# Master_sheet.net
KiCad netlist of a schematic drawn in Altium Designer
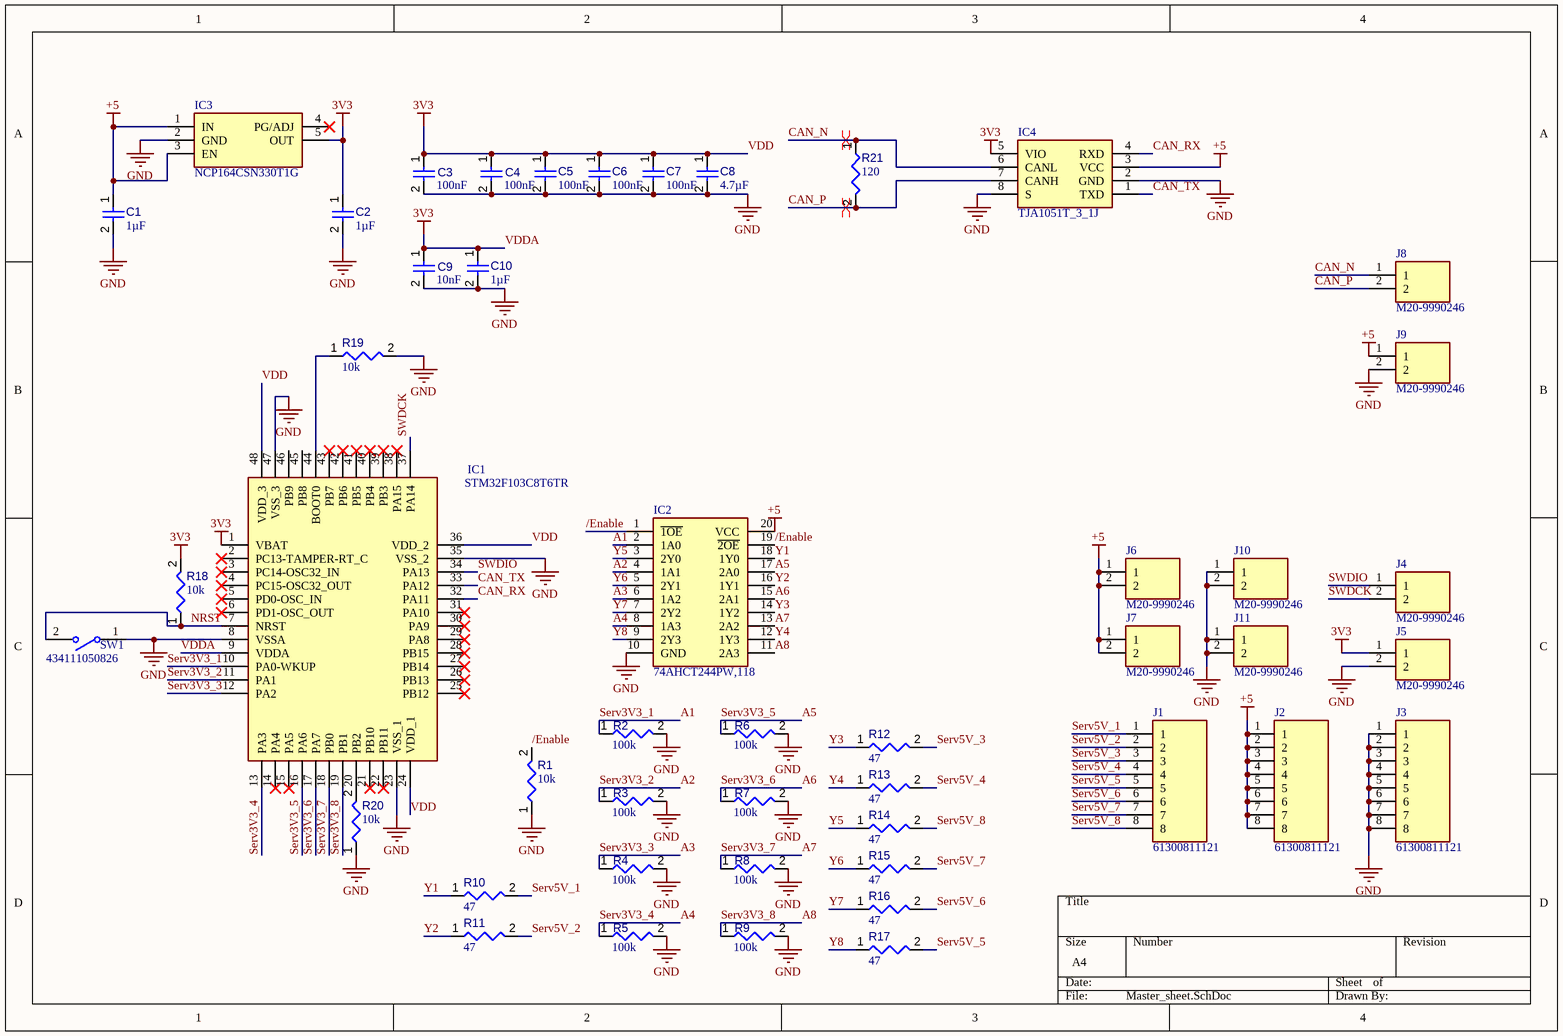
[diagram p0: Master_sheet.SchDoc]

(export (version "E")
  (design (tool "Eeschema 10.0.6"))
  (components
    (comp (ref "C1")
      (value "1µF")
      (footprint "CAPC1608X94X35NL15T15")
      (description "Chip Capacitor, 1 uF, +/- 10%, 16 V, 0603 (1608 Metric)")
      (fields (field (name "TOLERANCE") "10%") (field (name "Comment") "Capacitor 1 uF +/- 10% 16 V 0603"))
      (libsource (lib "CPRT Workspace") (part "CAP-NP-2"))
    )
    (comp (ref "C2")
      (value "1µF")
      (footprint "CAPC1608X94X35NL15T15")
      (description "Chip Capacitor, 1 uF, +/- 10%, 16 V, 0603 (1608 Metric)")
      (fields (field (name "TOLERANCE") "10%") (field (name "Comment") "Capacitor 1 uF +/- 10% 16 V 0603"))
      (libsource (lib "CPRT Workspace") (part "CAP-NP-2"))
    )
    (comp (ref "C3")
      (value "100nF")
      (footprint "CAPC1608X94X35NL15T15")
      (description "Chip Capacitor, 1 uF, +/- 10%, 16 V, 0603 (1608 Metric)")
      (fields (field (name "TOLERANCE") "10%") (field (name "Comment") "Capacitor 1 uF +/- 10% 16 V 0603"))
      (libsource (lib "CPRT Workspace") (part "CAP-NP-2"))
    )
    (comp (ref "C4")
      (value "100nF")
      (footprint "CAPC1608X94X35NL15T15")
      (description "Chip Capacitor, 1 uF, +/- 10%, 16 V, 0603 (1608 Metric)")
      (fields (field (name "TOLERANCE") "10%") (field (name "Comment") "Capacitor 1 uF +/- 10% 16 V 0603"))
      (libsource (lib "CPRT Workspace") (part "CAP-NP-2"))
    )
    (comp (ref "C5")
      (value "100nF")
      (footprint "CAPC1608X94X35NL15T15")
      (description "Chip Capacitor, 1 uF, +/- 10%, 16 V, 0603 (1608 Metric)")
      (fields (field (name "TOLERANCE") "10%") (field (name "Comment") "Capacitor 1 uF +/- 10% 16 V 0603"))
      (libsource (lib "CPRT Workspace") (part "CAP-NP-2"))
    )
    (comp (ref "C6")
      (value "100nF")
      (footprint "CAPC1608X94X35NL15T15")
      (description "Chip Capacitor, 1 uF, +/- 10%, 16 V, 0603 (1608 Metric)")
      (fields (field (name "TOLERANCE") "10%") (field (name "Comment") "Capacitor 1 uF +/- 10% 16 V 0603"))
      (libsource (lib "CPRT Workspace") (part "CAP-NP-2"))
    )
    (comp (ref "C7")
      (value "100nF")
      (footprint "CAPC1608X94X35NL15T15")
      (description "Chip Capacitor, 1 uF, +/- 10%, 16 V, 0603 (1608 Metric)")
      (fields (field (name "TOLERANCE") "10%") (field (name "Comment") "Capacitor 1 uF +/- 10% 16 V 0603"))
      (libsource (lib "CPRT Workspace") (part "CAP-NP-2"))
    )
    (comp (ref "C8")
      (value "4.7µF")
      (footprint "CAPC1608X94X35NL15T15")
      (description "Chip Capacitor, 1 uF, +/- 10%, 16 V, 0603 (1608 Metric)")
      (fields (field (name "TOLERANCE") "10%") (field (name "Comment") "Capacitor 1 uF +/- 10% 16 V 0603"))
      (libsource (lib "CPRT Workspace") (part "CAP-NP-2"))
    )
    (comp (ref "C9")
      (value "10nF")
      (footprint "CAPC1608X94X35NL15T15")
      (description "Chip Capacitor, 1 uF, +/- 10%, 16 V, 0603 (1608 Metric)")
      (fields (field (name "TOLERANCE") "10%") (field (name "Comment") "Capacitor 1 uF +/- 10% 16 V 0603"))
      (libsource (lib "CPRT Workspace") (part "CAP-NP-2"))
    )
    (comp (ref "C10")
      (value "1µF")
      (footprint "CAPC1608X94X35NL15T15")
      (description "Chip Capacitor, 1 uF, +/- 10%, 16 V, 0603 (1608 Metric)")
      (fields (field (name "TOLERANCE") "10%") (field (name "Comment") "Capacitor 1 uF +/- 10% 16 V 0603"))
      (libsource (lib "CPRT Workspace") (part "CAP-NP-2"))
    )
    (comp (ref "IC1")
      (value "STM32F103C8T6TR")
      (footprint "SamacSys:QFP50P900X900X160-48N")
      (description "Integrated Circuit")
      (fields (field (name "MOUSER PART NUMBER") "511-STM32F103C8T6TR"))
      (libsource (lib "*") (part "STM32F103C8T6TR"))
    )
    (comp (ref "IC2")
      (value "74AHCT244PW,118")
      (footprint "SamacSys:SOP65P640X110-20N")
      (description "Integrated Circuit")
      (fields (field (name "MOUSER PART NUMBER") "771-AHCT244PW118"))
      (libsource (lib "*") (part "74AHCT244PW,118"))
    )
    (comp (ref "IC3")
      (value "NCP164CSN330T1G")
      (footprint "SamacSys:SOT95P275X110-5N")
      (description "Integrated Circuit")
      (fields (field (name "MOUSER PART NUMBER") "863-NCP164CSN330T1G"))
      (libsource (lib "*") (part "NCP164CSN330T1G"))
    )
    (comp (ref "IC4")
      (value "TJA1051T_3_1J")
      (footprint "SamacSys:SOIC127P600X175-8N")
      (description "Integrated Circuit")
      (fields
        (field (name "MANUFACTURER_PART_NUMBER") "TJA1051T/3/1J")
        (field (name "MOUSER PART NUMBER") "771-TJA1051T/3/1J")
      )
      (libsource (lib "*") (part "TJA1051T_3_1J"))
    )
    (comp (ref "J1")
      (value "61300811121")
      (footprint "SamacSys:HDRV8W64P0X254_1X8_2032X254X854P")
      (description "Connector")
      (fields (field (name "MOUSER PART NUMBER") "710-61300811121"))
      (libsource (lib "*") (part "61300811121"))
    )
    (comp (ref "J2")
      (value "61300811121")
      (footprint "SamacSys:HDRV8W64P0X254_1X8_2032X254X854P")
      (description "Connector")
      (fields (field (name "MOUSER PART NUMBER") "710-61300811121"))
      (libsource (lib "*") (part "61300811121"))
    )
    (comp (ref "J3")
      (value "61300811121")
      (footprint "SamacSys:HDRV8W64P0X254_1X8_2032X254X854P")
      (description "Connector")
      (fields (field (name "MOUSER PART NUMBER") "710-61300811121"))
      (libsource (lib "*") (part "61300811121"))
    )
    (comp (ref "J4")
      (value "M20-9990246")
      (footprint "SamacSys:HDRV2W66P0X254_1X2_508X254X874P")
      (description "Connector")
      (fields (field (name "MOUSER PART NUMBER") "855-M20-9990246"))
      (libsource (lib "*") (part "M20-9990246"))
    )
    (comp (ref "J5")
      (value "M20-9990246")
      (footprint "SamacSys:HDRV2W66P0X254_1X2_508X254X874P")
      (description "Connector")
      (fields (field (name "MOUSER PART NUMBER") "855-M20-9990246"))
      (libsource (lib "*") (part "M20-9990246"))
    )
    (comp (ref "J6")
      (value "M20-9990246")
      (footprint "SamacSys:HDRV2W66P0X254_1X2_508X254X874P")
      (description "Connector")
      (fields (field (name "MOUSER PART NUMBER") "855-M20-9990246"))
      (libsource (lib "*") (part "M20-9990246"))
    )
    (comp (ref "J7")
      (value "M20-9990246")
      (footprint "SamacSys:HDRV2W66P0X254_1X2_508X254X874P")
      (description "Connector")
      (fields (field (name "MOUSER PART NUMBER") "855-M20-9990246"))
      (libsource (lib "*") (part "M20-9990246"))
    )
    (comp (ref "J8")
      (value "M20-9990246")
      (footprint "SamacSys:HDRV2W66P0X254_1X2_508X254X874P")
      (description "Connector")
      (fields (field (name "MOUSER PART NUMBER") "855-M20-9990246"))
      (libsource (lib "*") (part "M20-9990246"))
    )
    (comp (ref "J9")
      (value "M20-9990246")
      (footprint "SamacSys:HDRV2W66P0X254_1X2_508X254X874P")
      (description "Connector")
      (fields (field (name "MOUSER PART NUMBER") "855-M20-9990246"))
      (libsource (lib "*") (part "M20-9990246"))
    )
    (comp (ref "J10")
      (value "M20-9990246")
      (footprint "SamacSys:HDRV2W66P0X254_1X2_508X254X874P")
      (description "Connector")
      (fields (field (name "MOUSER PART NUMBER") "855-M20-9990246"))
      (libsource (lib "*") (part "M20-9990246"))
    )
    (comp (ref "J11")
      (value "M20-9990246")
      (footprint "SamacSys:HDRV2W66P0X254_1X2_508X254X874P")
      (description "Connector")
      (fields (field (name "MOUSER PART NUMBER") "855-M20-9990246"))
      (libsource (lib "*") (part "M20-9990246"))
    )
    (comp (ref "R1")
      (value "10k")
      (footprint "RESC1608X55X25ML10T15")
      (description "Chip Resistor, 100 KOhm, +/- 1%, 0.1 W, -55 to 155 degC, 0603 (1608 Metric)")
      (fields (field (name "TOLERANCE") "1%") (field (name "POWER") "100mW"))
      (libsource (lib "CPRT Workspace") (part "RES-2"))
    )
    (comp (ref "R2")
      (value "100k")
      (footprint "RESC1608X55X25ML10T15")
      (description "Chip Resistor, 100 KOhm, +/- 1%, 0.1 W, -55 to 155 degC, 0603 (1608 Metric)")
      (fields (field (name "TOLERANCE") "1%") (field (name "POWER") "100mW"))
      (libsource (lib "CPRT Workspace") (part "RES-2"))
    )
    (comp (ref "R3")
      (value "100k")
      (footprint "RESC1608X55X25ML10T15")
      (description "Chip Resistor, 100 KOhm, +/- 1%, 0.1 W, -55 to 155 degC, 0603 (1608 Metric)")
      (fields (field (name "TOLERANCE") "1%") (field (name "POWER") "100mW"))
      (libsource (lib "CPRT Workspace") (part "RES-2"))
    )
    (comp (ref "R4")
      (value "100k")
      (footprint "RESC1608X55X25ML10T15")
      (description "Chip Resistor, 100 KOhm, +/- 1%, 0.1 W, -55 to 155 degC, 0603 (1608 Metric)")
      (fields (field (name "TOLERANCE") "1%") (field (name "POWER") "100mW"))
      (libsource (lib "CPRT Workspace") (part "RES-2"))
    )
    (comp (ref "R5")
      (value "100k")
      (footprint "RESC1608X55X25ML10T15")
      (description "Chip Resistor, 100 KOhm, +/- 1%, 0.1 W, -55 to 155 degC, 0603 (1608 Metric)")
      (fields (field (name "TOLERANCE") "1%") (field (name "POWER") "100mW"))
      (libsource (lib "CPRT Workspace") (part "RES-2"))
    )
    (comp (ref "R6")
      (value "100k")
      (footprint "RESC1608X55X25ML10T15")
      (description "Chip Resistor, 100 KOhm, +/- 1%, 0.1 W, -55 to 155 degC, 0603 (1608 Metric)")
      (fields (field (name "TOLERANCE") "1%") (field (name "POWER") "100mW"))
      (libsource (lib "CPRT Workspace") (part "RES-2"))
    )
    (comp (ref "R7")
      (value "100k")
      (footprint "RESC1608X55X25ML10T15")
      (description "Chip Resistor, 100 KOhm, +/- 1%, 0.1 W, -55 to 155 degC, 0603 (1608 Metric)")
      (fields (field (name "TOLERANCE") "1%") (field (name "POWER") "100mW"))
      (libsource (lib "CPRT Workspace") (part "RES-2"))
    )
    (comp (ref "R8")
      (value "100k")
      (footprint "RESC1608X55X25ML10T15")
      (description "Chip Resistor, 100 KOhm, +/- 1%, 0.1 W, -55 to 155 degC, 0603 (1608 Metric)")
      (fields (field (name "TOLERANCE") "1%") (field (name "POWER") "100mW"))
      (libsource (lib "CPRT Workspace") (part "RES-2"))
    )
    (comp (ref "R9")
      (value "100k")
      (footprint "RESC1608X55X25ML10T15")
      (description "Chip Resistor, 100 KOhm, +/- 1%, 0.1 W, -55 to 155 degC, 0603 (1608 Metric)")
      (fields (field (name "TOLERANCE") "1%") (field (name "POWER") "100mW"))
      (libsource (lib "CPRT Workspace") (part "RES-2"))
    )
    (comp (ref "R10")
      (value "47")
      (footprint "RESC1608X55X25ML10T15")
      (description "Chip Resistor, 100 KOhm, +/- 1%, 0.1 W, -55 to 155 degC, 0603 (1608 Metric)")
      (fields (field (name "TOLERANCE") "1%") (field (name "POWER") "100mW"))
      (libsource (lib "CPRT Workspace") (part "RES-2"))
    )
    (comp (ref "R11")
      (value "47")
      (footprint "RESC1608X55X25ML10T15")
      (description "Chip Resistor, 100 KOhm, +/- 1%, 0.1 W, -55 to 155 degC, 0603 (1608 Metric)")
      (fields (field (name "TOLERANCE") "1%") (field (name "POWER") "100mW"))
      (libsource (lib "CPRT Workspace") (part "RES-2"))
    )
    (comp (ref "R12")
      (value "47")
      (footprint "RESC1608X55X25ML10T15")
      (description "Chip Resistor, 100 KOhm, +/- 1%, 0.1 W, -55 to 155 degC, 0603 (1608 Metric)")
      (fields (field (name "TOLERANCE") "1%") (field (name "POWER") "100mW"))
      (libsource (lib "CPRT Workspace") (part "RES-2"))
    )
    (comp (ref "R13")
      (value "47")
      (footprint "RESC1608X55X25ML10T15")
      (description "Chip Resistor, 100 KOhm, +/- 1%, 0.1 W, -55 to 155 degC, 0603 (1608 Metric)")
      (fields (field (name "TOLERANCE") "1%") (field (name "POWER") "100mW"))
      (libsource (lib "CPRT Workspace") (part "RES-2"))
    )
    (comp (ref "R14")
      (value "47")
      (footprint "RESC1608X55X25ML10T15")
      (description "Chip Resistor, 100 KOhm, +/- 1%, 0.1 W, -55 to 155 degC, 0603 (1608 Metric)")
      (fields (field (name "TOLERANCE") "1%") (field (name "POWER") "100mW"))
      (libsource (lib "CPRT Workspace") (part "RES-2"))
    )
    (comp (ref "R15")
      (value "47")
      (footprint "RESC1608X55X25ML10T15")
      (description "Chip Resistor, 100 KOhm, +/- 1%, 0.1 W, -55 to 155 degC, 0603 (1608 Metric)")
      (fields (field (name "TOLERANCE") "1%") (field (name "POWER") "100mW"))
      (libsource (lib "CPRT Workspace") (part "RES-2"))
    )
    (comp (ref "R16")
      (value "47")
      (footprint "RESC1608X55X25ML10T15")
      (description "Chip Resistor, 100 KOhm, +/- 1%, 0.1 W, -55 to 155 degC, 0603 (1608 Metric)")
      (fields (field (name "TOLERANCE") "1%") (field (name "POWER") "100mW"))
      (libsource (lib "CPRT Workspace") (part "RES-2"))
    )
    (comp (ref "R17")
      (value "47")
      (footprint "RESC1608X55X25ML10T15")
      (description "Chip Resistor, 100 KOhm, +/- 1%, 0.1 W, -55 to 155 degC, 0603 (1608 Metric)")
      (fields (field (name "TOLERANCE") "1%") (field (name "POWER") "100mW"))
      (libsource (lib "CPRT Workspace") (part "RES-2"))
    )
    (comp (ref "R18")
      (value "10k")
      (footprint "RESC1608X55X25ML10T15")
      (description "Chip Resistor, 100 KOhm, +/- 1%, 0.1 W, -55 to 155 degC, 0603 (1608 Metric)")
      (fields (field (name "TOLERANCE") "1%") (field (name "POWER") "100mW"))
      (libsource (lib "CPRT Workspace") (part "RES-2"))
    )
    (comp (ref "R19")
      (value "10k")
      (footprint "RESC1608X55X25ML10T15")
      (description "Chip Resistor, 100 KOhm, +/- 1%, 0.1 W, -55 to 155 degC, 0603 (1608 Metric)")
      (fields (field (name "TOLERANCE") "1%") (field (name "POWER") "100mW"))
      (libsource (lib "CPRT Workspace") (part "RES-2"))
    )
    (comp (ref "R20")
      (value "10k")
      (footprint "RESC1608X55X25ML10T15")
      (description "Chip Resistor, 100 KOhm, +/- 1%, 0.1 W, -55 to 155 degC, 0603 (1608 Metric)")
      (fields (field (name "TOLERANCE") "1%") (field (name "POWER") "100mW"))
      (libsource (lib "CPRT Workspace") (part "RES-2"))
    )
    (comp (ref "R21")
      (value "120")
      (footprint "RESC1608X55X25ML10T15")
      (description "Chip Resistor, 100 KOhm, +/- 1%, 0.1 W, -55 to 155 degC, 0603 (1608 Metric)")
      (fields (field (name "TOLERANCE") "1%") (field (name "POWER") "100mW"))
      (libsource (lib "CPRT Workspace") (part "RES-2"))
    )
    (comp (ref "SW1")
      (value "434111050826")
      (footprint "434111050826")
      (libsource (lib "CPRT Workspace") (part "SPST-NO_2P"))
    )
  )
  (nets
    (net (code "1") (name "+5") (class "Default")
      (node (ref "C1") (pin "1") (pinfunction "1_1") (pintype "passive"))
      (node (ref "IC2") (pin "20") (pinfunction "VCC_20") (pintype "passive"))
      (node (ref "IC3") (pin "1") (pinfunction "IN_1") (pintype "passive"))
      (node (ref "IC3") (pin "3") (pinfunction "EN_3") (pintype "passive"))
      (node (ref "IC4") (pin "3") (pinfunction "VCC_3") (pintype "passive"))
      (node (ref "J2") (pin "1") (pinfunction "1_1") (pintype "passive"))
      (node (ref "J2") (pin "2") (pinfunction "2_2") (pintype "passive"))
      (node (ref "J2") (pin "3") (pinfunction "3_3") (pintype "passive"))
      (node (ref "J2") (pin "4") (pinfunction "4_4") (pintype "passive"))
      (node (ref "J2") (pin "5") (pinfunction "5_5") (pintype "passive"))
      (node (ref "J2") (pin "6") (pinfunction "6_6") (pintype "passive"))
      (node (ref "J2") (pin "7") (pinfunction "7_7") (pintype "passive"))
      (node (ref "J2") (pin "8") (pinfunction "8_8") (pintype "passive"))
      (node (ref "J6") (pin "1") (pinfunction "1_1") (pintype "passive"))
      (node (ref "J6") (pin "2") (pinfunction "2_2") (pintype "passive"))
      (node (ref "J7") (pin "1") (pinfunction "1_1") (pintype "passive"))
      (node (ref "J7") (pin "2") (pinfunction "2_2") (pintype "passive"))
      (node (ref "J9") (pin "1") (pinfunction "1_1") (pintype "passive"))
    )
    (net (code "2") (name "/A1") (class "Default")
      (node (ref "IC1") (pin "10") (pinfunction "PA0-WKUP_10") (pintype "passive"))
      (node (ref "IC2") (pin "2") (pinfunction "1A0_2") (pintype "passive"))
      (node (ref "R2") (pin "1") (pinfunction "1_1") (pintype "passive"))
    )
    (net (code "3") (name "/A2") (class "Default")
      (node (ref "IC1") (pin "11") (pinfunction "PA1_11") (pintype "passive"))
      (node (ref "IC2") (pin "4") (pinfunction "1A1_4") (pintype "passive"))
      (node (ref "R3") (pin "1") (pinfunction "1_1") (pintype "passive"))
    )
    (net (code "4") (name "/A3") (class "Default")
      (node (ref "IC1") (pin "12") (pinfunction "PA2_12") (pintype "passive"))
      (node (ref "IC2") (pin "6") (pinfunction "1A2_6") (pintype "passive"))
      (node (ref "R4") (pin "1") (pinfunction "1_1") (pintype "passive"))
    )
    (net (code "5") (name "/A4") (class "Default")
      (node (ref "IC1") (pin "13") (pinfunction "PA3_13") (pintype "passive"))
      (node (ref "IC2") (pin "8") (pinfunction "1A3_8") (pintype "passive"))
      (node (ref "R5") (pin "1") (pinfunction "1_1") (pintype "passive"))
    )
    (net (code "6") (name "/A5") (class "Default")
      (node (ref "IC1") (pin "16") (pinfunction "PA6_16") (pintype "passive"))
      (node (ref "IC2") (pin "17") (pinfunction "2A0_17") (pintype "passive"))
      (node (ref "R6") (pin "1") (pinfunction "1_1") (pintype "passive"))
    )
    (net (code "7") (name "/A6") (class "Default")
      (node (ref "IC1") (pin "17") (pinfunction "PA7_17") (pintype "passive"))
      (node (ref "IC2") (pin "15") (pinfunction "2A1_15") (pintype "passive"))
      (node (ref "R7") (pin "1") (pinfunction "1_1") (pintype "passive"))
    )
    (net (code "8") (name "/A7") (class "Default")
      (node (ref "IC1") (pin "18") (pinfunction "PB0_18") (pintype "passive"))
      (node (ref "IC2") (pin "13") (pinfunction "2A2_13") (pintype "passive"))
      (node (ref "R8") (pin "1") (pinfunction "1_1") (pintype "passive"))
    )
    (net (code "9") (name "/A8") (class "Default")
      (node (ref "IC1") (pin "19") (pinfunction "PB1_19") (pintype "passive"))
      (node (ref "IC2") (pin "11") (pinfunction "2A3_11") (pintype "passive"))
      (node (ref "R9") (pin "1") (pinfunction "1_1") (pintype "passive"))
    )
    (net (code "10") (name "/CAN_N") (class "Default")
      (node (ref "IC4") (pin "6") (pinfunction "CANL_6") (pintype "passive"))
      (node (ref "J8") (pin "1") (pinfunction "1_1") (pintype "passive"))
      (node (ref "R21") (pin "1") (pinfunction "1_1") (pintype "passive"))
    )
    (net (code "11") (name "/CAN_P") (class "Default")
      (node (ref "IC4") (pin "7") (pinfunction "CANH_7") (pintype "passive"))
      (node (ref "J8") (pin "2") (pinfunction "2_2") (pintype "passive"))
      (node (ref "R21") (pin "2") (pinfunction "2_2") (pintype "passive"))
    )
    (net (code "12") (name "/CAN_RX") (class "Default")
      (node (ref "IC1") (pin "32") (pinfunction "PA11_32") (pintype "passive"))
      (node (ref "IC4") (pin "4") (pinfunction "RXD_4") (pintype "passive"))
    )
    (net (code "13") (name "/CAN_TX") (class "Default")
      (node (ref "IC1") (pin "33") (pinfunction "PA12_33") (pintype "passive"))
      (node (ref "IC4") (pin "1") (pinfunction "TXD_1") (pintype "passive"))
    )
    (net (code "14") (name "/NRST") (class "Default")
      (node (ref "IC1") (pin "7") (pinfunction "NRST_7") (pintype "passive"))
      (node (ref "R18") (pin "1") (pinfunction "1_1") (pintype "passive"))
      (node (ref "SW1") (pin "2") (pinfunction "2_2") (pintype "passive"))
    )
    (net (code "15") (name "/SWDCK") (class "Default")
      (node (ref "IC1") (pin "37") (pinfunction "PA14_37") (pintype "passive"))
      (node (ref "J4") (pin "2") (pinfunction "2_2") (pintype "passive"))
    )
    (net (code "16") (name "/SWDIO") (class "Default")
      (node (ref "IC1") (pin "34") (pinfunction "PA13_34") (pintype "passive"))
      (node (ref "J4") (pin "1") (pinfunction "1_1") (pintype "passive"))
    )
    (net (code "17") (name "/Serv5V_1") (class "Default")
      (node (ref "J1") (pin "1") (pinfunction "1_1") (pintype "passive"))
      (node (ref "R10") (pin "2") (pinfunction "2_2") (pintype "passive"))
    )
    (net (code "18") (name "/Serv5V_2") (class "Default")
      (node (ref "J1") (pin "2") (pinfunction "2_2") (pintype "passive"))
      (node (ref "R11") (pin "2") (pinfunction "2_2") (pintype "passive"))
    )
    (net (code "19") (name "/Serv5V_3") (class "Default")
      (node (ref "J1") (pin "3") (pinfunction "3_3") (pintype "passive"))
      (node (ref "R12") (pin "2") (pinfunction "2_2") (pintype "passive"))
    )
    (net (code "20") (name "/Serv5V_4") (class "Default")
      (node (ref "J1") (pin "4") (pinfunction "4_4") (pintype "passive"))
      (node (ref "R13") (pin "2") (pinfunction "2_2") (pintype "passive"))
    )
    (net (code "21") (name "/Serv5V_5") (class "Default")
      (node (ref "J1") (pin "5") (pinfunction "5_5") (pintype "passive"))
      (node (ref "R17") (pin "2") (pinfunction "2_2") (pintype "passive"))
    )
    (net (code "22") (name "/Serv5V_6") (class "Default")
      (node (ref "J1") (pin "6") (pinfunction "6_6") (pintype "passive"))
      (node (ref "R16") (pin "2") (pinfunction "2_2") (pintype "passive"))
    )
    (net (code "23") (name "/Serv5V_7") (class "Default")
      (node (ref "J1") (pin "7") (pinfunction "7_7") (pintype "passive"))
      (node (ref "R15") (pin "2") (pinfunction "2_2") (pintype "passive"))
    )
    (net (code "24") (name "/Serv5V_8") (class "Default")
      (node (ref "J1") (pin "8") (pinfunction "8_8") (pintype "passive"))
      (node (ref "R14") (pin "2") (pinfunction "2_2") (pintype "passive"))
    )
    (net (code "25") (name "/Y1") (class "Default")
      (node (ref "IC2") (pin "18") (pinfunction "1Y0_18") (pintype "passive"))
      (node (ref "R10") (pin "1") (pinfunction "1_1") (pintype "passive"))
    )
    (net (code "26") (name "/Y2") (class "Default")
      (node (ref "IC2") (pin "16") (pinfunction "1Y1_16") (pintype "passive"))
      (node (ref "R11") (pin "1") (pinfunction "1_1") (pintype "passive"))
    )
    (net (code "27") (name "/Y3") (class "Default")
      (node (ref "IC2") (pin "14") (pinfunction "1Y2_14") (pintype "passive"))
      (node (ref "R12") (pin "1") (pinfunction "1_1") (pintype "passive"))
    )
    (net (code "28") (name "/Y4") (class "Default")
      (node (ref "IC2") (pin "12") (pinfunction "1Y3_12") (pintype "passive"))
      (node (ref "R13") (pin "1") (pinfunction "1_1") (pintype "passive"))
    )
    (net (code "29") (name "/Y5") (class "Default")
      (node (ref "IC2") (pin "3") (pinfunction "2Y0_3") (pintype "passive"))
      (node (ref "R14") (pin "1") (pinfunction "1_1") (pintype "passive"))
    )
    (net (code "30") (name "/Y6") (class "Default")
      (node (ref "IC2") (pin "5") (pinfunction "2Y1_5") (pintype "passive"))
      (node (ref "R15") (pin "1") (pinfunction "1_1") (pintype "passive"))
    )
    (net (code "31") (name "/Y7") (class "Default")
      (node (ref "IC2") (pin "7") (pinfunction "2Y2_7") (pintype "passive"))
      (node (ref "R16") (pin "1") (pinfunction "1_1") (pintype "passive"))
    )
    (net (code "32") (name "/Y8") (class "Default")
      (node (ref "IC2") (pin "9") (pinfunction "2Y3_9") (pintype "passive"))
      (node (ref "R17") (pin "1") (pinfunction "1_1") (pintype "passive"))
    )
    (net (code "33") (name "/{slash}Enable") (class "Default")
      (node (ref "IC2") (pin "1") (pinfunction "~{1OE}_1") (pintype "passive"))
      (node (ref "IC2") (pin "19") (pinfunction "~{2OE}_19") (pintype "passive"))
      (node (ref "R1") (pin "2") (pinfunction "2_2") (pintype "passive"))
    )
    (net (code "34") (name "3V3") (class "Default")
      (node (ref "C10") (pin "1") (pinfunction "1_1") (pintype "passive"))
      (node (ref "C2") (pin "1") (pinfunction "1_1") (pintype "passive"))
      (node (ref "C3") (pin "1") (pinfunction "1_1") (pintype "passive"))
      (node (ref "C4") (pin "1") (pinfunction "1_1") (pintype "passive"))
      (node (ref "C5") (pin "1") (pinfunction "1_1") (pintype "passive"))
      (node (ref "C6") (pin "1") (pinfunction "1_1") (pintype "passive"))
      (node (ref "C7") (pin "1") (pinfunction "1_1") (pintype "passive"))
      (node (ref "C8") (pin "1") (pinfunction "1_1") (pintype "passive"))
      (node (ref "C9") (pin "1") (pinfunction "1_1") (pintype "passive"))
      (node (ref "IC1") (pin "1") (pinfunction "VBAT_1") (pintype "passive"))
      (node (ref "IC1") (pin "24") (pinfunction "VDD_1_24") (pintype "passive"))
      (node (ref "IC1") (pin "36") (pinfunction "VDD_2_36") (pintype "passive"))
      (node (ref "IC1") (pin "48") (pinfunction "VDD_3_48") (pintype "passive"))
      (node (ref "IC1") (pin "9") (pinfunction "VDDA_9") (pintype "passive"))
      (node (ref "IC3") (pin "5") (pinfunction "OUT_5") (pintype "passive"))
      (node (ref "IC4") (pin "5") (pinfunction "VIO_5") (pintype "passive"))
      (node (ref "J5") (pin "1") (pinfunction "1_1") (pintype "passive"))
      (node (ref "R18") (pin "2") (pinfunction "2_2") (pintype "passive"))
    )
    (net (code "35") (name "GND") (class "Default")
      (node (ref "C1") (pin "2") (pinfunction "2_2") (pintype "passive"))
      (node (ref "C10") (pin "2") (pinfunction "2_2") (pintype "passive"))
      (node (ref "C2") (pin "2") (pinfunction "2_2") (pintype "passive"))
      (node (ref "C3") (pin "2") (pinfunction "2_2") (pintype "passive"))
      (node (ref "C4") (pin "2") (pinfunction "2_2") (pintype "passive"))
      (node (ref "C5") (pin "2") (pinfunction "2_2") (pintype "passive"))
      (node (ref "C6") (pin "2") (pinfunction "2_2") (pintype "passive"))
      (node (ref "C7") (pin "2") (pinfunction "2_2") (pintype "passive"))
      (node (ref "C8") (pin "2") (pinfunction "2_2") (pintype "passive"))
      (node (ref "C9") (pin "2") (pinfunction "2_2") (pintype "passive"))
      (node (ref "IC1") (pin "23") (pinfunction "VSS_1_23") (pintype "passive"))
      (node (ref "IC1") (pin "35") (pinfunction "VSS_2_35") (pintype "passive"))
      (node (ref "IC1") (pin "47") (pinfunction "VSS_3_47") (pintype "passive"))
      (node (ref "IC1") (pin "8") (pinfunction "VSSA_8") (pintype "passive"))
      (node (ref "IC2") (pin "10") (pinfunction "GND_10") (pintype "passive"))
      (node (ref "IC3") (pin "2") (pinfunction "GND_2") (pintype "passive"))
      (node (ref "IC4") (pin "2") (pinfunction "GND_2") (pintype "passive"))
      (node (ref "IC4") (pin "8") (pinfunction "S_8") (pintype "passive"))
      (node (ref "J10") (pin "1") (pinfunction "1_1") (pintype "passive"))
      (node (ref "J10") (pin "2") (pinfunction "2_2") (pintype "passive"))
      (node (ref "J11") (pin "1") (pinfunction "1_1") (pintype "passive"))
      (node (ref "J11") (pin "2") (pinfunction "2_2") (pintype "passive"))
      (node (ref "J3") (pin "1") (pinfunction "1_1") (pintype "passive"))
      (node (ref "J3") (pin "2") (pinfunction "2_2") (pintype "passive"))
      (node (ref "J3") (pin "3") (pinfunction "3_3") (pintype "passive"))
      (node (ref "J3") (pin "4") (pinfunction "4_4") (pintype "passive"))
      (node (ref "J3") (pin "5") (pinfunction "5_5") (pintype "passive"))
      (node (ref "J3") (pin "6") (pinfunction "6_6") (pintype "passive"))
      (node (ref "J3") (pin "7") (pinfunction "7_7") (pintype "passive"))
      (node (ref "J3") (pin "8") (pinfunction "8_8") (pintype "passive"))
      (node (ref "J5") (pin "2") (pinfunction "2_2") (pintype "passive"))
      (node (ref "J9") (pin "2") (pinfunction "2_2") (pintype "passive"))
      (node (ref "R1") (pin "1") (pinfunction "1_1") (pintype "passive"))
      (node (ref "R19") (pin "2") (pinfunction "2_2") (pintype "passive"))
      (node (ref "R2") (pin "2") (pinfunction "2_2") (pintype "passive"))
      (node (ref "R20") (pin "1") (pinfunction "1_1") (pintype "passive"))
      (node (ref "R3") (pin "2") (pinfunction "2_2") (pintype "passive"))
      (node (ref "R4") (pin "2") (pinfunction "2_2") (pintype "passive"))
      (node (ref "R5") (pin "2") (pinfunction "2_2") (pintype "passive"))
      (node (ref "R6") (pin "2") (pinfunction "2_2") (pintype "passive"))
      (node (ref "R7") (pin "2") (pinfunction "2_2") (pintype "passive"))
      (node (ref "R8") (pin "2") (pinfunction "2_2") (pintype "passive"))
      (node (ref "R9") (pin "2") (pinfunction "2_2") (pintype "passive"))
      (node (ref "SW1") (pin "1") (pinfunction "1_1") (pintype "passive"))
    )
    (net (code "36") (name "Net-(IC1-BOOT0)") (class "Default")
      (node (ref "IC1") (pin "44") (pinfunction "BOOT0_44") (pintype "passive"))
      (node (ref "R19") (pin "1") (pinfunction "1_1") (pintype "passive"))
    )
    (net (code "37") (name "Net-(IC1-PB2)") (class "Default")
      (node (ref "IC1") (pin "20") (pinfunction "PB2_20") (pintype "passive"))
      (node (ref "R20") (pin "2") (pinfunction "2_2") (pintype "passive"))
    )
    (net (code "38") (name "unconnected-(IC1-PA4-Pad14)") (class "Default")
      (node (ref "IC1") (pin "14") (pinfunction "PA4_14") (pintype "passive+no_connect"))
    )
    (net (code "39") (name "unconnected-(IC1-PA5-Pad15)") (class "Default")
      (node (ref "IC1") (pin "15") (pinfunction "PA5_15") (pintype "passive+no_connect"))
    )
    (net (code "40") (name "unconnected-(IC1-PA8-Pad29)") (class "Default")
      (node (ref "IC1") (pin "29") (pinfunction "PA8_29") (pintype "passive+no_connect"))
    )
    (net (code "41") (name "unconnected-(IC1-PA9-Pad30)") (class "Default")
      (node (ref "IC1") (pin "30") (pinfunction "PA9_30") (pintype "passive+no_connect"))
    )
    (net (code "42") (name "unconnected-(IC1-PA10-Pad31)") (class "Default")
      (node (ref "IC1") (pin "31") (pinfunction "PA10_31") (pintype "passive+no_connect"))
    )
    (net (code "43") (name "unconnected-(IC1-PA15-Pad38)") (class "Default")
      (node (ref "IC1") (pin "38") (pinfunction "PA15_38") (pintype "passive+no_connect"))
    )
    (net (code "44") (name "unconnected-(IC1-PB3-Pad39)") (class "Default")
      (node (ref "IC1") (pin "39") (pinfunction "PB3_39") (pintype "passive+no_connect"))
    )
    (net (code "45") (name "unconnected-(IC1-PB4-Pad40)") (class "Default")
      (node (ref "IC1") (pin "40") (pinfunction "PB4_40") (pintype "passive+no_connect"))
    )
    (net (code "46") (name "unconnected-(IC1-PB5-Pad41)") (class "Default")
      (node (ref "IC1") (pin "41") (pinfunction "PB5_41") (pintype "passive+no_connect"))
    )
    (net (code "47") (name "unconnected-(IC1-PB6-Pad42)") (class "Default")
      (node (ref "IC1") (pin "42") (pinfunction "PB6_42") (pintype "passive+no_connect"))
    )
    (net (code "48") (name "unconnected-(IC1-PB7-Pad43)") (class "Default")
      (node (ref "IC1") (pin "43") (pinfunction "PB7_43") (pintype "passive+no_connect"))
    )
    (net (code "49") (name "unconnected-(IC1-PB8-Pad45)") (class "Default")
      (node (ref "IC1") (pin "45") (pinfunction "PB8_45") (pintype "passive"))
    )
    (net (code "50") (name "unconnected-(IC1-PB9-Pad46)") (class "Default")
      (node (ref "IC1") (pin "46") (pinfunction "PB9_46") (pintype "passive"))
    )
    (net (code "51") (name "unconnected-(IC1-PB10-Pad21)") (class "Default")
      (node (ref "IC1") (pin "21") (pinfunction "PB10_21") (pintype "passive+no_connect"))
    )
    (net (code "52") (name "unconnected-(IC1-PB11-Pad22)") (class "Default")
      (node (ref "IC1") (pin "22") (pinfunction "PB11_22") (pintype "passive+no_connect"))
    )
    (net (code "53") (name "unconnected-(IC1-PB12-Pad25)") (class "Default")
      (node (ref "IC1") (pin "25") (pinfunction "PB12_25") (pintype "passive+no_connect"))
    )
    (net (code "54") (name "unconnected-(IC1-PB13-Pad26)") (class "Default")
      (node (ref "IC1") (pin "26") (pinfunction "PB13_26") (pintype "passive+no_connect"))
    )
    (net (code "55") (name "unconnected-(IC1-PB14-Pad27)") (class "Default")
      (node (ref "IC1") (pin "27") (pinfunction "PB14_27") (pintype "passive+no_connect"))
    )
    (net (code "56") (name "unconnected-(IC1-PB15-Pad28)") (class "Default")
      (node (ref "IC1") (pin "28") (pinfunction "PB15_28") (pintype "passive+no_connect"))
    )
    (net (code "57") (name "unconnected-(IC1-PC13-TAMPER-RT_C-Pad2)") (class "Default")
      (node (ref "IC1") (pin "2") (pinfunction "PC13-TAMPER-RT_C_2") (pintype "passive+no_connect"))
    )
    (net (code "58") (name "unconnected-(IC1-PC14-OSC32_IN-Pad3)") (class "Default")
      (node (ref "IC1") (pin "3") (pinfunction "PC14-OSC32_IN_3") (pintype "passive+no_connect"))
    )
    (net (code "59") (name "unconnected-(IC1-PC15-OSC32_OUT-Pad4)") (class "Default")
      (node (ref "IC1") (pin "4") (pinfunction "PC15-OSC32_OUT_4") (pintype "passive+no_connect"))
    )
    (net (code "60") (name "unconnected-(IC1-PD0-OSC_IN-Pad5)") (class "Default")
      (node (ref "IC1") (pin "5") (pinfunction "PD0-OSC_IN_5") (pintype "passive+no_connect"))
    )
    (net (code "61") (name "unconnected-(IC1-PD1-OSC_OUT-Pad6)") (class "Default")
      (node (ref "IC1") (pin "6") (pinfunction "PD1-OSC_OUT_6") (pintype "passive+no_connect"))
    )
    (net (code "62") (name "unconnected-(IC3-PG{slash}ADJ-Pad4)") (class "Default")
      (node (ref "IC3") (pin "4") (pinfunction "PG/ADJ_4") (pintype "passive+no_connect"))
    )
  )
)
